# heater.net
KiCad netlist of a schematic drawn in Altium Designer
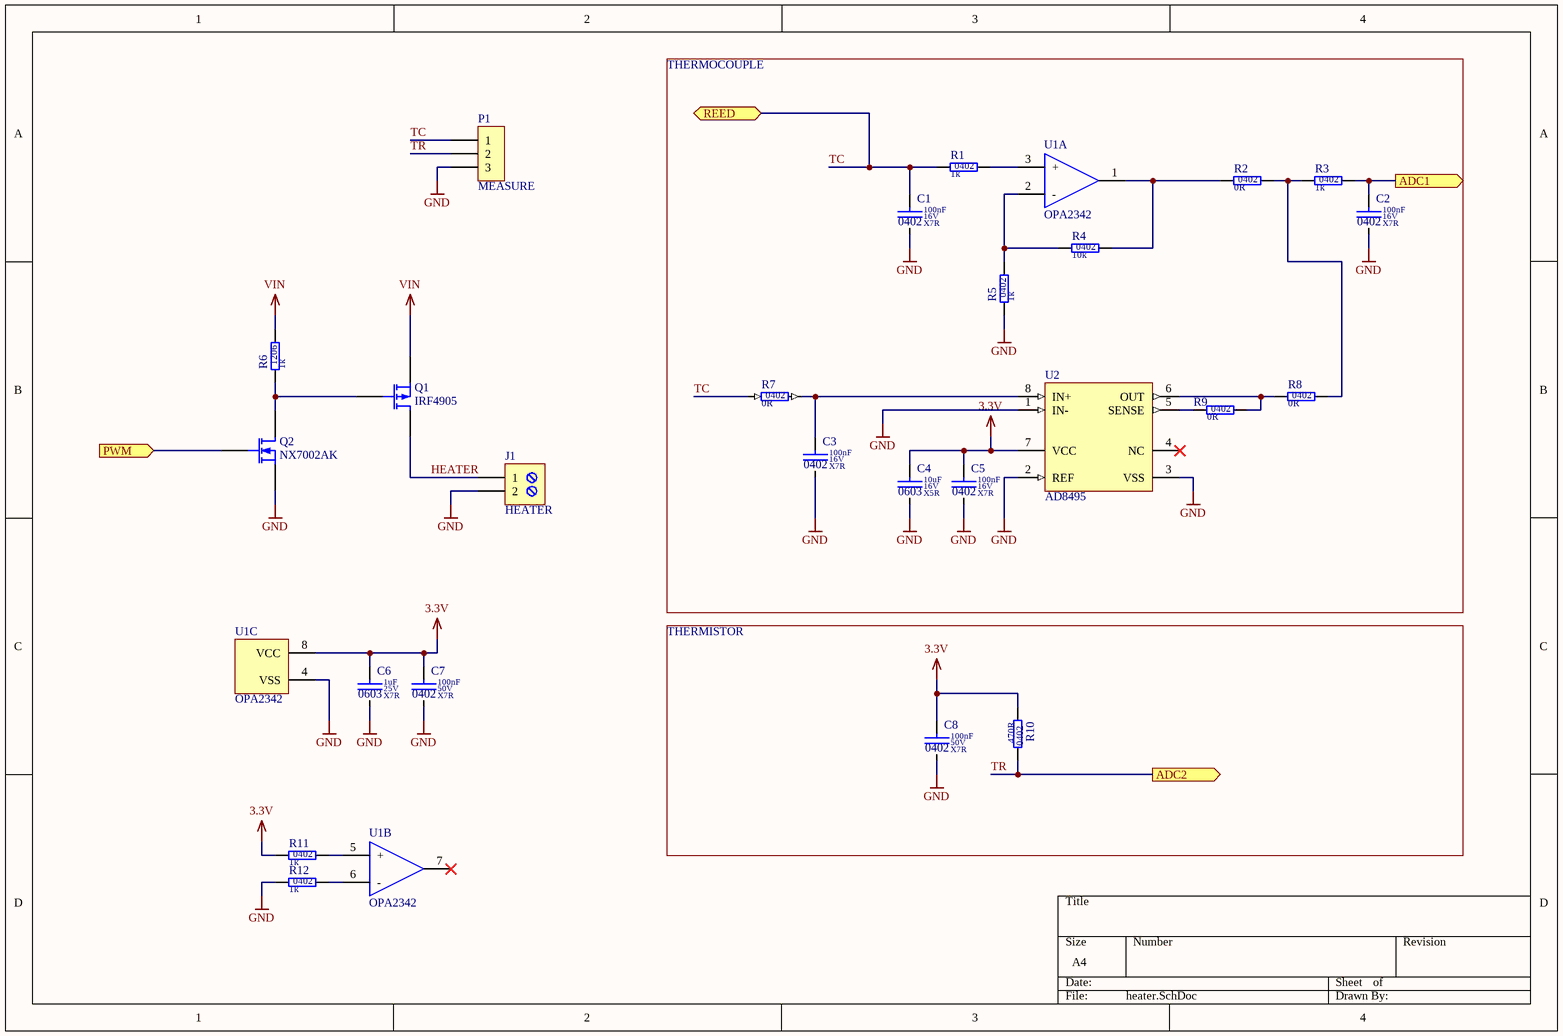
[diagram p0: heater.SchDoc]

(export (version "E")
  (design (tool "Eeschema 10.0.6"))
  (components
    (comp (ref "C1")
      (value "100nF")
      (footprint "C_0402_1005")
      (description "Capacitor")
      (fields
        (field (name "DIELECTRIC") "X7R")
        (field (name "VOLTAGE") "16V")
        (field (name "SCH_FOOTPRINT") "0402")
        (field (name "PART NUMBER") "C_100nF_16V_X7R_0402_10")
        (field (name "MANUFACTURER") "Murata")
      )
      (libsource (lib "Library") (part "C"))
    )
    (comp (ref "C2")
      (value "100nF")
      (footprint "C_0402_1005")
      (description "Capacitor")
      (fields
        (field (name "DIELECTRIC") "X7R")
        (field (name "VOLTAGE") "16V")
        (field (name "SCH_FOOTPRINT") "0402")
        (field (name "PART NUMBER") "C_100nF_16V_X7R_0402_10")
        (field (name "MANUFACTURER") "Murata")
      )
      (libsource (lib "Library") (part "C"))
    )
    (comp (ref "C3")
      (value "100nF")
      (footprint "C_0402_1005")
      (description "Capacitor")
      (fields
        (field (name "DIELECTRIC") "X7R")
        (field (name "VOLTAGE") "16V")
        (field (name "SCH_FOOTPRINT") "0402")
        (field (name "PART NUMBER") "C_100nF_16V_X7R_0402_10")
        (field (name "MANUFACTURER") "Murata")
      )
      (libsource (lib "Library") (part "C"))
    )
    (comp (ref "C4")
      (value "10uF")
      (footprint "C_0603_1608")
      (description "Capacitor")
      (fields
        (field (name "DIELECTRIC") "X5R")
        (field (name "VOLTAGE") "16V")
        (field (name "SCH_FOOTPRINT") "0603")
        (field (name "PART NUMBER") "C_10uF_16V_X5R_0603_20")
        (field (name "MANUFACTURER") "Samsung Electro-Mechanics")
      )
      (libsource (lib "Library") (part "C"))
    )
    (comp (ref "C5")
      (value "100nF")
      (footprint "C_0402_1005")
      (description "Capacitor")
      (fields
        (field (name "DIELECTRIC") "X7R")
        (field (name "VOLTAGE") "16V")
        (field (name "SCH_FOOTPRINT") "0402")
        (field (name "PART NUMBER") "C_100nF_16V_X7R_0402_10")
        (field (name "MANUFACTURER") "Murata")
      )
      (libsource (lib "Library") (part "C"))
    )
    (comp (ref "C6")
      (value "1uF")
      (footprint "C_0603_1608")
      (description "Capacitor")
      (fields
        (field (name "DIELECTRIC") "X7R")
        (field (name "VOLTAGE") "25V")
        (field (name "SCH_FOOTPRINT") "0603")
        (field (name "PART NUMBER") "C_1uF_25V_X7R_0603_10")
        (field (name "MANUFACTURER") "Samsung")
      )
      (libsource (lib "Library") (part "C"))
    )
    (comp (ref "C7")
      (value "100nF")
      (footprint "C_0402_1005")
      (description "Capacitor")
      (fields
        (field (name "DIELECTRIC") "X7R")
        (field (name "VOLTAGE") "50V")
        (field (name "SCH_FOOTPRINT") "0402")
        (field (name "PART NUMBER") "C_100nF_50V_X7R_0402_10")
        (field (name "MANUFACTURER") "Murata")
      )
      (libsource (lib "Library") (part "C"))
    )
    (comp (ref "C8")
      (value "100nF")
      (footprint "C_0402_1005")
      (description "Capacitor")
      (fields
        (field (name "DIELECTRIC") "X7R")
        (field (name "VOLTAGE") "50V")
        (field (name "SCH_FOOTPRINT") "0402")
        (field (name "PART NUMBER") "C_100nF_50V_X7R_0402_10")
        (field (name "MANUFACTURER") "Murata")
      )
      (libsource (lib "Library") (part "C"))
    )
    (comp (ref "J1")
      (value "HEATER")
      (footprint "J_ARK2")
      (description "ARK Screw terminal, 2-Pin")
      (fields (field (name "PART NUMBER") "J_TB-5.0-P-2P") (field (name "MANUFACTURER") "DEGSON ELECTRONICS"))
      (libsource (lib "Library") (part "J_ARK2"))
    )
    (comp (ref "P1")
      (value "MEASURE")
      (footprint "P_HEADER_1x3_2.54_ANGLE")
      (description "Pin Header")
      (fields (field (name "PART NUMBER") "P_HEADER_1x3_2.54_ANGLE") (field (name "MANUFACTURER") "Molex"))
      (libsource (lib "Library") (part "P_HEADER_1x3"))
    )
    (comp (ref "Q1")
      (value "IRF4905")
      (footprint "IRF4905")
      (description "PMOS TO-220")
      (libsource (lib "soldering_station") (part "IRF4905"))
    )
    (comp (ref "Q2")
      (value "NX7002AK")
      (footprint "NX7002AK.215")
      (description "Tranzystor: N-MOSFET; unipolarny; 60V; 0,12A; 325mW; SOT23")
      (libsource (lib "soldering_station") (part "NX7002AK.215"))
    )
    (comp (ref "R1")
      (value "1k")
      (footprint "R_0402_1005")
      (fields
        (field (name "SCH_FOOTPRINT") "0402")
        (field (name "PART NUMBER") "R_1k_0402_1")
        (field (name "VOLTAGE") "50V")
        (field (name "POWER") "63mW")
      )
      (libsource (lib "Library") (part "R"))
    )
    (comp (ref "R2")
      (value "0R")
      (footprint "R_0402_1005")
      (fields
        (field (name "SCH_FOOTPRINT") "0402")
        (field (name "PART NUMBER") "R_0R_0402_5")
        (field (name "VOLTAGE") "50V")
        (field (name "POWER") "100mW")
      )
      (libsource (lib "Library") (part "R"))
    )
    (comp (ref "R3")
      (value "1k")
      (footprint "R_0402_1005")
      (fields
        (field (name "SCH_FOOTPRINT") "0402")
        (field (name "PART NUMBER") "R_1k_0402_1")
        (field (name "VOLTAGE") "50V")
        (field (name "POWER") "63mW")
      )
      (libsource (lib "Library") (part "R"))
    )
    (comp (ref "R4")
      (value "10k")
      (footprint "R_0402_1005")
      (fields
        (field (name "SCH_FOOTPRINT") "0402")
        (field (name "PART NUMBER") "R_10k_0402_1")
        (field (name "VOLTAGE") "50V")
        (field (name "POWER") "63mW")
      )
      (libsource (lib "Library") (part "R"))
    )
    (comp (ref "R5")
      (value "1k")
      (footprint "R_0402_1005")
      (fields
        (field (name "SCH_FOOTPRINT") "0402")
        (field (name "PART NUMBER") "R_1k_0402_1")
        (field (name "VOLTAGE") "50V")
        (field (name "POWER") "63mW")
      )
      (libsource (lib "Library") (part "R"))
    )
    (comp (ref "R6")
      (value "1k")
      (footprint "R_1206_3216")
      (fields
        (field (name "SCH_FOOTPRINT") "1206")
        (field (name "PART NUMBER") "R_47k_1206_1")
        (field (name "VOLTAGE") "200V")
        (field (name "POWER") "500mW")
      )
      (libsource (lib "Library") (part "R"))
    )
    (comp (ref "R7")
      (value "0R")
      (footprint "R_0402_1005")
      (fields
        (field (name "SCH_FOOTPRINT") "0402")
        (field (name "PART NUMBER") "R_0R_0402_5")
        (field (name "VOLTAGE") "50V")
        (field (name "POWER") "100mW")
      )
      (libsource (lib "") (part "R_1"))
    )
    (comp (ref "R8")
      (value "0R")
      (footprint "R_0402_1005")
      (fields
        (field (name "SCH_FOOTPRINT") "0402")
        (field (name "PART NUMBER") "R_0R_0402_5")
        (field (name "VOLTAGE") "50V")
        (field (name "POWER") "100mW")
      )
      (libsource (lib "Library") (part "R"))
    )
    (comp (ref "R9")
      (value "0R")
      (footprint "R_0402_1005")
      (fields
        (field (name "SCH_FOOTPRINT") "0402")
        (field (name "PART NUMBER") "R_0R_0402_5")
        (field (name "VOLTAGE") "50V")
        (field (name "POWER") "100mW")
      )
      (libsource (lib "Library") (part "R"))
    )
    (comp (ref "R10")
      (value "470R")
      (footprint "R_0402_1005")
      (fields
        (field (name "SCH_FOOTPRINT") "0402")
        (field (name "PART NUMBER") "R_470R_0402_1")
        (field (name "VOLTAGE") "50V")
        (field (name "POWER") "63mW")
      )
      (libsource (lib "Library") (part "R"))
    )
    (comp (ref "R11")
      (value "1k")
      (footprint "R_0402_1005")
      (fields
        (field (name "SCH_FOOTPRINT") "0402")
        (field (name "PART NUMBER") "R_1k_0402_1")
        (field (name "VOLTAGE") "50V")
        (field (name "POWER") "63mW")
      )
      (libsource (lib "Library") (part "R"))
    )
    (comp (ref "R12")
      (value "1k")
      (footprint "R_0402_1005")
      (fields
        (field (name "SCH_FOOTPRINT") "0402")
        (field (name "PART NUMBER") "R_1k_0402_1")
        (field (name "VOLTAGE") "50V")
        (field (name "POWER") "63mW")
      )
      (libsource (lib "Library") (part "R"))
    )
    (comp (ref "U1")
      (value "OPA2342")
      (footprint "OPA2342")
      (description "Wzmacniacz operacyjny; 1MHz; 2,7÷5,5V; Kanały: 2; SO8")
      (libsource (lib "soldering_station") (part "OPA2342"))
    )
    (comp (ref "U2")
      (value "AD8495")
      (footprint "AD8494")
      (description "Precision Thermocouple Amplifiers\r\nwith Cold Junction Compensation")
      (libsource (lib "soldering_station") (part "AD8495"))
    )
  )
  (nets
    (net (code "1") (name "/ADC1") (class "Default")
      (node (ref "C2") (pin "1") (pinfunction "1_1") (pintype "passive"))
      (node (ref "R3") (pin "2") (pinfunction "2_2") (pintype "passive"))
    )
    (net (code "2") (name "/HEATER") (class "Default")
      (node (ref "J1") (pin "1") (pinfunction "1_1") (pintype "passive"))
      (node (ref "Q1") (pin "2") (pinfunction "D_2") (pintype "passive"))
    )
    (net (code "3") (name "/PWM") (class "Default")
      (node (ref "Q2") (pin "1") (pinfunction "G_1") (pintype "passive"))
    )
    (net (code "4") (name "/TC") (class "Default")
      (node (ref "C1") (pin "1") (pinfunction "1_1") (pintype "passive"))
      (node (ref "P1") (pin "1") (pinfunction "1_1") (pintype "passive"))
      (node (ref "R1") (pin "1") (pinfunction "1_1") (pintype "passive"))
      (node (ref "R7") (pin "1") (pinfunction "1_1") (pintype "input"))
    )
    (net (code "5") (name "/TR") (class "Default")
      (node (ref "P1") (pin "2") (pinfunction "2_2") (pintype "passive"))
      (node (ref "R10") (pin "2") (pinfunction "2_2") (pintype "passive"))
    )
    (net (code "6") (name "3.3V") (class "Default")
      (node (ref "C4") (pin "1") (pinfunction "1_1") (pintype "passive"))
      (node (ref "C5") (pin "1") (pinfunction "1_1") (pintype "passive"))
      (node (ref "C6") (pin "1") (pinfunction "1_1") (pintype "passive"))
      (node (ref "C7") (pin "1") (pinfunction "1_1") (pintype "passive"))
      (node (ref "C8") (pin "1") (pinfunction "1_1") (pintype "passive"))
      (node (ref "R10") (pin "1") (pinfunction "1_1") (pintype "passive"))
      (node (ref "R11") (pin "1") (pinfunction "1_1") (pintype "passive"))
      (node (ref "U1") (pin "8") (pinfunction "VCC_8") (pintype "power_in"))
      (node (ref "U2") (pin "7") (pinfunction "VCC_7") (pintype "power_in"))
    )
    (net (code "7") (name "GND") (class "Default")
      (node (ref "C1") (pin "2") (pinfunction "2_2") (pintype "passive"))
      (node (ref "C2") (pin "2") (pinfunction "2_2") (pintype "passive"))
      (node (ref "C3") (pin "2") (pinfunction "2_2") (pintype "passive"))
      (node (ref "C4") (pin "2") (pinfunction "2_2") (pintype "passive"))
      (node (ref "C5") (pin "2") (pinfunction "2_2") (pintype "passive"))
      (node (ref "C6") (pin "2") (pinfunction "2_2") (pintype "passive"))
      (node (ref "C7") (pin "2") (pinfunction "2_2") (pintype "passive"))
      (node (ref "C8") (pin "2") (pinfunction "2_2") (pintype "passive"))
      (node (ref "J1") (pin "2") (pinfunction "2_2") (pintype "passive"))
      (node (ref "P1") (pin "3") (pinfunction "3_3") (pintype "passive"))
      (node (ref "Q2") (pin "2") (pinfunction "S_2") (pintype "passive"))
      (node (ref "R12") (pin "1") (pinfunction "1_1") (pintype "passive"))
      (node (ref "R5") (pin "1") (pinfunction "1_1") (pintype "passive"))
      (node (ref "U1") (pin "4") (pinfunction "VSS_4") (pintype "power_in"))
      (node (ref "U2") (pin "1") (pinfunction "IN-_1") (pintype "input"))
      (node (ref "U2") (pin "2") (pinfunction "REF_2") (pintype "input"))
      (node (ref "U2") (pin "3") (pinfunction "VSS_3") (pintype "power_in"))
    )
    (net (code "8") (name "Net-(Q1-G)") (class "Default")
      (node (ref "Q1") (pin "1") (pinfunction "G_1") (pintype "passive"))
      (node (ref "Q2") (pin "3") (pinfunction "D_3") (pintype "passive"))
      (node (ref "R6") (pin "1") (pinfunction "1_1") (pintype "passive"))
    )
    (net (code "9") (name "Net-(R2-Pad2)") (class "Default")
      (node (ref "R2") (pin "2") (pinfunction "2_2") (pintype "passive"))
      (node (ref "R3") (pin "1") (pinfunction "1_1") (pintype "passive"))
      (node (ref "R8") (pin "2") (pinfunction "2_2") (pintype "passive"))
    )
    (net (code "10") (name "Net-(U1A-+)") (class "Default")
      (node (ref "R1") (pin "2") (pinfunction "2_2") (pintype "passive"))
      (node (ref "U1") (pin "3") (pinfunction "+_3") (pintype "passive"))
    )
    (net (code "11") (name "Net-(U1A--)") (class "Default")
      (node (ref "R4") (pin "1") (pinfunction "1_1") (pintype "passive"))
      (node (ref "R5") (pin "2") (pinfunction "2_2") (pintype "passive"))
      (node (ref "U1") (pin "2") (pinfunction "-_2") (pintype "passive"))
    )
    (net (code "12") (name "Net-(U1A-OUT)") (class "Default")
      (node (ref "R2") (pin "1") (pinfunction "1_1") (pintype "passive"))
      (node (ref "R4") (pin "2") (pinfunction "2_2") (pintype "passive"))
      (node (ref "U1") (pin "1") (pinfunction "OUT_1") (pintype "passive"))
    )
    (net (code "13") (name "Net-(U1B-+)") (class "Default")
      (node (ref "R11") (pin "2") (pinfunction "2_2") (pintype "passive"))
      (node (ref "U1") (pin "5") (pinfunction "+_5") (pintype "passive"))
    )
    (net (code "14") (name "Net-(U1B--)") (class "Default")
      (node (ref "R12") (pin "2") (pinfunction "2_2") (pintype "passive"))
      (node (ref "U1") (pin "6") (pinfunction "-_6") (pintype "passive"))
    )
    (net (code "15") (name "Net-(U2-IN+)") (class "Default")
      (node (ref "C3") (pin "1") (pinfunction "1_1") (pintype "passive"))
      (node (ref "R7") (pin "2") (pinfunction "2_2") (pintype "output"))
      (node (ref "U2") (pin "8") (pinfunction "IN+_8") (pintype "input"))
    )
    (net (code "16") (name "Net-(U2-OUT)") (class "Default")
      (node (ref "R8") (pin "1") (pinfunction "1_1") (pintype "passive"))
      (node (ref "R9") (pin "2") (pinfunction "2_2") (pintype "passive"))
      (node (ref "U2") (pin "6") (pinfunction "OUT_6") (pintype "output"))
    )
    (net (code "17") (name "Net-(U2-SENSE)") (class "Default")
      (node (ref "R9") (pin "1") (pinfunction "1_1") (pintype "passive"))
      (node (ref "U2") (pin "5") (pinfunction "SENSE_5") (pintype "output"))
    )
    (net (code "18") (name "VIN") (class "Default")
      (node (ref "Q1") (pin "3") (pinfunction "S_3") (pintype "passive"))
      (node (ref "R6") (pin "2") (pinfunction "2_2") (pintype "passive"))
    )
    (net (code "19") (name "unconnected-(U1B-OUT-Pad7)") (class "Default")
      (node (ref "U1") (pin "7") (pinfunction "OUT_7") (pintype "passive+no_connect"))
    )
    (net (code "20") (name "unconnected-(U2-NC-Pad4)") (class "Default")
      (node (ref "U2") (pin "4") (pinfunction "NC_4") (pintype "passive+no_connect"))
    )
  )
)
